# RFM300EVB_V01.net
KiCad netlist of a schematic drawn in Altium Designer
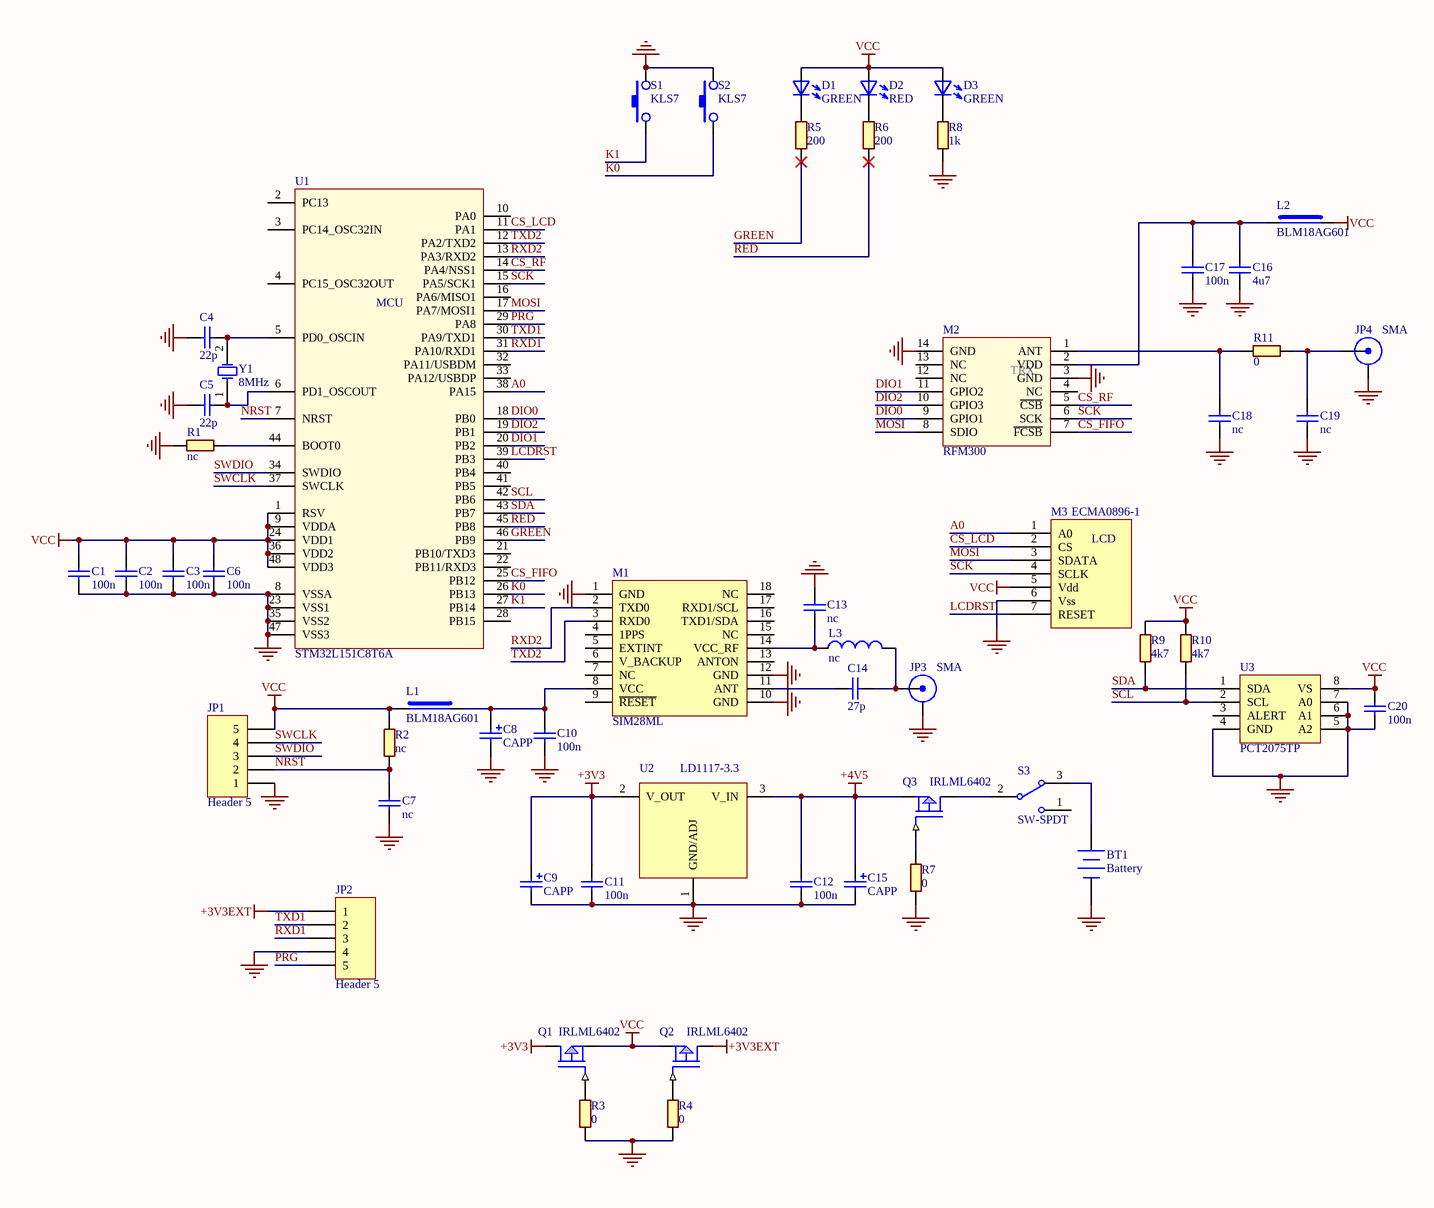
[diagram p0: RFM300EVB_V01.SchDoc]

(export (version "E")
  (design (tool "Eeschema 10.0.6"))
  (components
    (comp (ref "BT1")
      (value "Battery")
      (footprint "3AAAHOLDER")
      (description "Multicell Battery")
      (fields (field (name "PUBLISHER") "Altium Limited"))
      (libsource (lib "Miscellaneous Devices") (part "Battery"))
    )
    (comp (ref "C1") (value "100n") (footprint "C-0603") (libsource (lib "Discrete") (part "CAPN")))
    (comp (ref "C2") (value "100n") (footprint "C-0603") (libsource (lib "Discrete") (part "CAPN")))
    (comp (ref "C3") (value "100n") (footprint "C-0603") (libsource (lib "Discrete") (part "CAPN")))
    (comp (ref "C4") (value "22p") (footprint "C-0603") (libsource (lib "Discrete") (part "CAPN")))
    (comp (ref "C5") (value "22p") (footprint "C-0603") (libsource (lib "Discrete") (part "CAPN")))
    (comp (ref "C6") (value "100n") (footprint "C-0603") (libsource (lib "Discrete") (part "CAPN")))
    (comp (ref "C7") (value "nc") (footprint "C-0603") (libsource (lib "Discrete") (part "CAPN")))
    (comp (ref "C8") (value "CAPP") (footprint "C-TANTAL-B") (libsource (lib "Discrete") (part "CAPP")))
    (comp (ref "C9") (value "CAPP") (footprint "C-TANTAL-B") (libsource (lib "Discrete") (part "CAPP")))
    (comp (ref "C10") (value "100n") (footprint "C-0603") (libsource (lib "Discrete") (part "CAPN")))
    (comp (ref "C11") (value "100n") (footprint "C-0603") (libsource (lib "Discrete") (part "CAPN")))
    (comp (ref "C12") (value "100n") (footprint "C-0603") (libsource (lib "Discrete") (part "CAPN")))
    (comp (ref "C13") (value "nc") (footprint "C-0603") (libsource (lib "Discrete") (part "CAPN")))
    (comp (ref "C14") (value "27p") (footprint "C-0603") (libsource (lib "Discrete") (part "CAPN")))
    (comp (ref "C15") (value "CAPP") (footprint "C-TANTAL-B") (libsource (lib "Discrete") (part "CAPP")))
    (comp (ref "C16") (value "4u7") (footprint "C-0805") (libsource (lib "Discrete") (part "CAPN")))
    (comp (ref "C17") (value "100n") (footprint "C-0603") (libsource (lib "Discrete") (part "CAPN")))
    (comp (ref "C18") (value "nc") (footprint "C-0603") (libsource (lib "Discrete") (part "CAPN")))
    (comp (ref "C19") (value "nc") (footprint "C-0603") (libsource (lib "Discrete") (part "CAPN")))
    (comp (ref "C20") (value "100n") (footprint "C-0603") (libsource (lib "Discrete") (part "CAPN")))
    (comp (ref "D1") (value "GREEN") (footprint "LED_0805") (libsource (lib "Discrete") (part "DLED")))
    (comp (ref "D2") (value "RED") (footprint "LED_0805") (libsource (lib "Discrete") (part "DLED")))
    (comp (ref "D3") (value "GREEN") (footprint "LED_0805") (libsource (lib "Discrete") (part "DLED")))
    (comp (ref "JP1")
      (value "Header 5")
      (footprint "PLS1-5R")
      (description "Header, 5-Pin")
      (fields (field (name "PUBLISHER") "Altium Limited"))
      (libsource (lib "") (part "Header 5_1"))
    )
    (comp (ref "JP2")
      (value "Header 5")
      (footprint "PLS1-5R")
      (description "Header, 5-Pin")
      (fields (field (name "PUBLISHER") "Altium Limited"))
      (libsource (lib "Miscellaneous Connectors") (part "Header 5"))
    )
    (comp (ref "JP3")
      (value "SMA")
      (footprint "AMPHENOL_132357-11")
      (description "RF Connector")
      (libsource (lib "Connectors$switces") (part "X-004"))
    )
    (comp (ref "JP4")
      (value "SMA")
      (footprint "AMPHENOL_132357-11")
      (description "RF Connector")
      (libsource (lib "Connectors$switces") (part "X-004"))
    )
    (comp (ref "L1") (value "BLM18AG601") (footprint "L-0603") (libsource (lib "Discrete") (part "SUPRESOR")))
    (comp (ref "L2") (value "BLM18AG601") (footprint "L-0603") (libsource (lib "Discrete") (part "SUPRESOR")))
    (comp (ref "L3") (value "nc") (footprint "L-0603") (libsource (lib "Discrete") (part "L")))
    (comp (ref "M1")
      (value "SIM28ML")
      (footprint "LGA18_GNSS")
      (libsource (lib "Cellular_GNSS") (part "SIM28ML"))
    )
    (comp (ref "M2")
      (value "RFM300")
      (footprint "LGA14C200P2X7_1600X1600X200")
      (libsource (lib "RFtest") (part "RFM300"))
    )
    (comp (ref "M3") (value "ECMA0896-1") (footprint "PLS1-7") (libsource (lib "RCS-IMS") (part "ECMA0896")))
    (comp (ref "Q1") (value "IRLML6402") (footprint "SOT-23") (libsource (lib "Discrete") (part "IRLML6402")))
    (comp (ref "Q2") (value "IRLML6402") (footprint "SOT-23") (libsource (lib "Discrete") (part "IRLML6402")))
    (comp (ref "Q3") (value "IRLML6402") (footprint "SOT-23") (libsource (lib "Discrete") (part "IRLML6402")))
    (comp (ref "R1") (value "nc") (footprint "R-0603") (libsource (lib "") (part "RES_2")))
    (comp (ref "R2") (value "nc") (footprint "R-0603") (libsource (lib "Discrete") (part "RES")))
    (comp (ref "R3") (value "0") (footprint "R-0603") (libsource (lib "Discrete") (part "RES")))
    (comp (ref "R4") (value "0") (footprint "R-0603") (libsource (lib "Discrete") (part "RES")))
    (comp (ref "R5") (value "200") (footprint "R-0603") (libsource (lib "") (part "RES_1")))
    (comp (ref "R6") (value "200") (footprint "R-0603") (libsource (lib "") (part "RES_1")))
    (comp (ref "R7") (value "0") (footprint "R-0603") (libsource (lib "Discrete") (part "RES")))
    (comp (ref "R8") (value "1k") (footprint "R-0603") (libsource (lib "") (part "RES_1")))
    (comp (ref "R9") (value "4k7") (footprint "R-0603") (libsource (lib "Discrete") (part "RES")))
    (comp (ref "R10") (value "4k7") (footprint "R-0603") (libsource (lib "Discrete") (part "RES")))
    (comp (ref "R11") (value "0") (footprint "R-0603") (libsource (lib "") (part "RES_2")))
    (comp (ref "S1") (value "KLS7") (footprint "KLS7-TS3602") (libsource (lib "CLAP DM-WL-R2") (part "SW-1")))
    (comp (ref "S2") (value "KLS7") (footprint "KLS7-TS3602") (libsource (lib "CLAP DM-WL-R2") (part "SW-1")))
    (comp (ref "S3")
      (value "SW-SPDT")
      (footprint "SPDT_100mil")
      (description "SPDT Subminiature Toggle Switch, Right Angle Mounting, Vertical Actuation")
      (fields (field (name "PUBLISHER") "Altium Limited"))
      (libsource (lib "Miscellaneous Devices") (part "SW-SPDT"))
    )
    (comp (ref "U1")
      (value "STM32L151C8T6A")
      (footprint "LQFP-48")
      (libsource (lib "RFtest") (part "STM32L151C8T6"))
    )
    (comp (ref "U2")
      (value "LD1117-3.3")
      (footprint "SOT230P700X180-4N")
      (libsource (lib "SB") (part "LM1117_3.3"))
    )
    (comp (ref "U3") (value "PCT2075TP") (footprint "SOT1069-2") (libsource (lib "UL2016_v2") (part "TMP75")))
    (comp (ref "Y1")
      (value "8MHz")
      (footprint "HC49_3.5mm")
      (description "Crystal Oscillator")
      (fields (field (name "PUBLISHER") "Altium Limited"))
      (libsource (lib "Miscellaneous Devices") (part "XTAL"))
    )
  )
  (nets
    (net (code "1") (name "+3V3") (class "Default")
      (node (ref "C11") (pin "1") (pinfunction "1_1") (pintype "passive"))
      (node (ref "C9") (pin "2") (pinfunction "2_2") (pintype "passive"))
      (node (ref "Q1") (pin "3") (pinfunction "DRAIN_3") (pintype "passive"))
      (node (ref "U2") (pin "2") (pinfunction "V_OUT_2") (pintype "passive"))
    )
    (net (code "2") (name "+3V3EXT") (class "Default")
      (node (ref "JP2") (pin "1") (pinfunction "1_1") (pintype "passive"))
      (node (ref "Q2") (pin "3") (pinfunction "DRAIN_3") (pintype "passive"))
    )
    (net (code "3") (name "+4V5") (class "Default")
      (node (ref "C12") (pin "1") (pinfunction "1_1") (pintype "passive"))
      (node (ref "C15") (pin "2") (pinfunction "2_2") (pintype "passive"))
      (node (ref "Q3") (pin "2") (pinfunction "SOURCE_2") (pintype "passive"))
      (node (ref "U2") (pin "3") (pinfunction "V_IN_3") (pintype "passive"))
    )
    (net (code "4") (name "/A0") (class "Default")
      (node (ref "M3") (pin "1") (pinfunction "A0_1") (pintype "passive"))
      (node (ref "U1") (pin "38") (pinfunction "PA15_38") (pintype "passive"))
    )
    (net (code "5") (name "/CS_FIFO") (class "Default")
      (node (ref "M2") (pin "7") (pinfunction "~{FCSB}_7") (pintype "passive"))
      (node (ref "U1") (pin "25") (pinfunction "PB12_25") (pintype "passive"))
    )
    (net (code "6") (name "/CS_LCD") (class "Default")
      (node (ref "M3") (pin "2") (pinfunction "CS_2") (pintype "passive"))
      (node (ref "U1") (pin "11") (pinfunction "PA1_11") (pintype "passive"))
    )
    (net (code "7") (name "/CS_RF") (class "Default")
      (node (ref "M2") (pin "5") (pinfunction "~{CSB}_5") (pintype "passive"))
      (node (ref "U1") (pin "14") (pinfunction "PA4/NSS1_14") (pintype "passive"))
    )
    (net (code "8") (name "/DIO0") (class "Default")
      (node (ref "M2") (pin "9") (pinfunction "GPIO1_9") (pintype "passive"))
      (node (ref "U1") (pin "18") (pinfunction "PB0_18") (pintype "passive"))
    )
    (net (code "9") (name "/DIO1") (class "Default")
      (node (ref "M2") (pin "11") (pinfunction "GPIO2_11") (pintype "passive"))
      (node (ref "U1") (pin "20") (pinfunction "PB2_20") (pintype "passive"))
    )
    (net (code "10") (name "/DIO2") (class "Default")
      (node (ref "M2") (pin "10") (pinfunction "GPIO3_10") (pintype "passive"))
      (node (ref "U1") (pin "19") (pinfunction "PB1_19") (pintype "passive"))
    )
    (net (code "11") (name "/GREEN") (class "Default")
      (node (ref "R5") (pin "2") (pinfunction "2_2") (pintype "passive"))
      (node (ref "U1") (pin "46") (pinfunction "PB9_46") (pintype "passive"))
    )
    (net (code "12") (name "/K0") (class "Default")
      (node (ref "S2") (pin "1") (pinfunction "1_1") (pintype "passive"))
      (node (ref "U1") (pin "26") (pinfunction "PB13_26") (pintype "passive"))
    )
    (net (code "13") (name "/K1") (class "Default")
      (node (ref "S1") (pin "1") (pinfunction "1_1") (pintype "passive"))
      (node (ref "U1") (pin "27") (pinfunction "PB14_27") (pintype "passive"))
    )
    (net (code "14") (name "/LCDRST") (class "Default")
      (node (ref "M3") (pin "7") (pinfunction "RESET_7") (pintype "passive"))
      (node (ref "U1") (pin "39") (pinfunction "PB3_39") (pintype "passive"))
    )
    (net (code "15") (name "/MOSI") (class "Default")
      (node (ref "M2") (pin "8") (pinfunction "SDIO_8") (pintype "passive"))
      (node (ref "M3") (pin "3") (pinfunction "SDATA_3") (pintype "passive"))
      (node (ref "U1") (pin "17") (pinfunction "PA7/MOSI1_17") (pintype "passive"))
    )
    (net (code "16") (name "/NRST") (class "Default")
      (node (ref "C7") (pin "1") (pinfunction "1_1") (pintype "passive"))
      (node (ref "JP1") (pin "2") (pinfunction "2_2") (pintype "passive"))
      (node (ref "R2") (pin "1") (pinfunction "1_1") (pintype "passive"))
      (node (ref "U1") (pin "7") (pinfunction "NRST_7") (pintype "passive"))
    )
    (net (code "17") (name "/PRG") (class "Default")
      (node (ref "JP2") (pin "5") (pinfunction "5_5") (pintype "passive"))
      (node (ref "U1") (pin "29") (pinfunction "PA8_29") (pintype "passive"))
    )
    (net (code "18") (name "/RED") (class "Default")
      (node (ref "R6") (pin "2") (pinfunction "2_2") (pintype "passive"))
      (node (ref "U1") (pin "45") (pinfunction "PB8_45") (pintype "passive"))
    )
    (net (code "19") (name "/RXD1") (class "Default")
      (node (ref "JP2") (pin "3") (pinfunction "3_3") (pintype "passive"))
      (node (ref "U1") (pin "31") (pinfunction "PA10/RXD1_31") (pintype "passive"))
    )
    (net (code "20") (name "/RXD2") (class "Default")
      (node (ref "M1") (pin "2") (pinfunction "TXD0_2") (pintype "passive"))
      (node (ref "U1") (pin "13") (pinfunction "PA3/RXD2_13") (pintype "passive"))
    )
    (net (code "21") (name "/SCK") (class "Default")
      (node (ref "M2") (pin "6") (pinfunction "SCK_6") (pintype "passive"))
      (node (ref "M3") (pin "4") (pinfunction "SCLK_4") (pintype "passive"))
      (node (ref "U1") (pin "15") (pinfunction "PA5/SCK1_15") (pintype "passive"))
    )
    (net (code "22") (name "/SCL") (class "Default")
      (node (ref "R10") (pin "1") (pinfunction "1_1") (pintype "passive"))
      (node (ref "U1") (pin "42") (pinfunction "PB6_42") (pintype "passive"))
      (node (ref "U3") (pin "2") (pinfunction "SCL_2") (pintype "passive"))
    )
    (net (code "23") (name "/SDA") (class "Default")
      (node (ref "R9") (pin "1") (pinfunction "1_1") (pintype "passive"))
      (node (ref "U1") (pin "43") (pinfunction "PB7_43") (pintype "passive"))
      (node (ref "U3") (pin "1") (pinfunction "SDA_1") (pintype "passive"))
    )
    (net (code "24") (name "/SWCLK") (class "Default")
      (node (ref "JP1") (pin "4") (pinfunction "4_4") (pintype "passive"))
      (node (ref "U1") (pin "37") (pinfunction "SWCLK_37") (pintype "passive"))
    )
    (net (code "25") (name "/SWDIO") (class "Default")
      (node (ref "JP1") (pin "3") (pinfunction "3_3") (pintype "passive"))
      (node (ref "U1") (pin "34") (pinfunction "SWDIO_34") (pintype "passive"))
    )
    (net (code "26") (name "/TXD1") (class "Default")
      (node (ref "JP2") (pin "2") (pinfunction "2_2") (pintype "passive"))
      (node (ref "U1") (pin "30") (pinfunction "PA9/TXD1_30") (pintype "passive"))
    )
    (net (code "27") (name "/TXD2") (class "Default")
      (node (ref "M1") (pin "3") (pinfunction "RXD0_3") (pintype "passive"))
      (node (ref "U1") (pin "12") (pinfunction "PA2/TXD2_12") (pintype "passive"))
    )
    (net (code "28") (name "GND") (class "Default")
      (node (ref "BT1") (pin "2") (pinfunction "-_2") (pintype "passive"))
      (node (ref "C1") (pin "2") (pinfunction "2_2") (pintype "passive"))
      (node (ref "C10") (pin "2") (pinfunction "2_2") (pintype "passive"))
      (node (ref "C11") (pin "2") (pinfunction "2_2") (pintype "passive"))
      (node (ref "C12") (pin "2") (pinfunction "2_2") (pintype "passive"))
      (node (ref "C13") (pin "1") (pinfunction "1_1") (pintype "passive"))
      (node (ref "C15") (pin "1") (pinfunction "1_1") (pintype "passive"))
      (node (ref "C16") (pin "2") (pinfunction "2_2") (pintype "passive"))
      (node (ref "C17") (pin "2") (pinfunction "2_2") (pintype "passive"))
      (node (ref "C18") (pin "2") (pinfunction "2_2") (pintype "passive"))
      (node (ref "C19") (pin "2") (pinfunction "2_2") (pintype "passive"))
      (node (ref "C2") (pin "2") (pinfunction "2_2") (pintype "passive"))
      (node (ref "C20") (pin "2") (pinfunction "2_2") (pintype "passive"))
      (node (ref "C3") (pin "2") (pinfunction "2_2") (pintype "passive"))
      (node (ref "C4") (pin "1") (pinfunction "1_1") (pintype "passive"))
      (node (ref "C5") (pin "1") (pinfunction "1_1") (pintype "passive"))
      (node (ref "C6") (pin "2") (pinfunction "2_2") (pintype "passive"))
      (node (ref "C7") (pin "2") (pinfunction "2_2") (pintype "passive"))
      (node (ref "C8") (pin "1") (pinfunction "1_1") (pintype "passive"))
      (node (ref "C9") (pin "1") (pinfunction "1_1") (pintype "passive"))
      (node (ref "JP1") (pin "1") (pinfunction "1_1") (pintype "passive"))
      (node (ref "JP2") (pin "4") (pinfunction "4_4") (pintype "passive"))
      (node (ref "JP3") (pin "2") (pinfunction "Y_2") (pintype "passive"))
      (node (ref "JP4") (pin "2") (pinfunction "Y_2") (pintype "passive"))
      (node (ref "M1") (pin "1") (pinfunction "GND_1") (pintype "passive"))
      (node (ref "M1") (pin "10") (pinfunction "GND_10") (pintype "passive"))
      (node (ref "M1") (pin "12") (pinfunction "GND_12") (pintype "passive"))
      (node (ref "M2") (pin "14") (pinfunction "GND_14") (pintype "passive"))
      (node (ref "M2") (pin "3") (pinfunction "GND_3") (pintype "passive"))
      (node (ref "M3") (pin "6") (pinfunction "Vss_6") (pintype "passive"))
      (node (ref "R1") (pin "1") (pinfunction "1_1") (pintype "passive"))
      (node (ref "R3") (pin "1") (pinfunction "1_1") (pintype "passive"))
      (node (ref "R4") (pin "1") (pinfunction "1_1") (pintype "passive"))
      (node (ref "R7") (pin "1") (pinfunction "1_1") (pintype "passive"))
      (node (ref "R8") (pin "2") (pinfunction "2_2") (pintype "passive"))
      (node (ref "S1") (pin "2") (pinfunction "2_2") (pintype "passive"))
      (node (ref "S2") (pin "2") (pinfunction "2_2") (pintype "passive"))
      (node (ref "U1") (pin "23") (pinfunction "VSS1_23") (pintype "passive"))
      (node (ref "U1") (pin "35") (pinfunction "VSS2_35") (pintype "passive"))
      (node (ref "U1") (pin "47") (pinfunction "VSS3_47") (pintype "passive"))
      (node (ref "U1") (pin "8") (pinfunction "VSSA_8") (pintype "passive"))
      (node (ref "U2") (pin "1") (pinfunction "GND/ADJ_1") (pintype "passive"))
      (node (ref "U3") (pin "4") (pinfunction "GND_4") (pintype "passive"))
      (node (ref "U3") (pin "5") (pinfunction "A2_5") (pintype "passive"))
      (node (ref "U3") (pin "6") (pinfunction "A1_6") (pintype "passive"))
      (node (ref "U3") (pin "7") (pinfunction "A0_7") (pintype "passive"))
    )
    (net (code "29") (name "Net-(BT1-+)") (class "Default")
      (node (ref "BT1") (pin "1") (pinfunction "+_1") (pintype "passive"))
      (node (ref "S3") (pin "3") (pinfunction "3_3") (pintype "passive"))
    )
    (net (code "30") (name "Net-(D1-2)") (class "Default")
      (node (ref "D1") (pin "K") (pinfunction "2_K") (pintype "passive"))
      (node (ref "R5") (pin "1") (pinfunction "1_1") (pintype "passive"))
    )
    (net (code "31") (name "Net-(D2-2)") (class "Default")
      (node (ref "D2") (pin "K") (pinfunction "2_K") (pintype "passive"))
      (node (ref "R6") (pin "1") (pinfunction "1_1") (pintype "passive"))
    )
    (net (code "32") (name "Net-(D3-2)") (class "Default")
      (node (ref "D3") (pin "K") (pinfunction "2_K") (pintype "passive"))
      (node (ref "R8") (pin "1") (pinfunction "1_1") (pintype "passive"))
    )
    (net (code "33") (name "Net-(JP3-X)") (class "Default")
      (node (ref "C14") (pin "2") (pinfunction "2_2") (pintype "passive"))
      (node (ref "JP3") (pin "1") (pinfunction "X_1") (pintype "passive"))
      (node (ref "L3") (pin "2") (pinfunction "2_2") (pintype "passive"))
    )
    (net (code "34") (name "Net-(JP4-X)") (class "Default")
      (node (ref "C19") (pin "1") (pinfunction "1_1") (pintype "passive"))
      (node (ref "JP4") (pin "1") (pinfunction "X_1") (pintype "passive"))
      (node (ref "R11") (pin "2") (pinfunction "2_2") (pintype "passive"))
    )
    (net (code "35") (name "Net-(M1-ANT)") (class "Default")
      (node (ref "C14") (pin "1") (pinfunction "1_1") (pintype "passive"))
      (node (ref "M1") (pin "11") (pinfunction "ANT_11") (pintype "passive"))
    )
    (net (code "36") (name "Net-(M1-VCC)") (class "Default")
      (node (ref "C10") (pin "1") (pinfunction "1_1") (pintype "passive"))
      (node (ref "C8") (pin "2") (pinfunction "2_2") (pintype "passive"))
      (node (ref "L1") (pin "2") (pinfunction "2_2") (pintype "passive"))
      (node (ref "M1") (pin "8") (pinfunction "VCC_8") (pintype "passive"))
    )
    (net (code "37") (name "Net-(M1-VCC_RF)") (class "Default")
      (node (ref "C13") (pin "2") (pinfunction "2_2") (pintype "passive"))
      (node (ref "L3") (pin "1") (pinfunction "1_1") (pintype "passive"))
      (node (ref "M1") (pin "14") (pinfunction "VCC_RF_14") (pintype "passive"))
    )
    (net (code "38") (name "Net-(M2-ANT)") (class "Default")
      (node (ref "C18") (pin "1") (pinfunction "1_1") (pintype "passive"))
      (node (ref "M2") (pin "1") (pinfunction "ANT_1") (pintype "passive"))
      (node (ref "R11") (pin "1") (pinfunction "1_1") (pintype "passive"))
    )
    (net (code "39") (name "Net-(M2-VDD)") (class "Default")
      (node (ref "C16") (pin "1") (pinfunction "1_1") (pintype "passive"))
      (node (ref "C17") (pin "1") (pinfunction "1_1") (pintype "passive"))
      (node (ref "L2") (pin "2") (pinfunction "2_2") (pintype "passive"))
      (node (ref "M2") (pin "2") (pinfunction "VDD_2") (pintype "passive"))
    )
    (net (code "40") (name "Net-(Q1-GATE)") (class "Default")
      (node (ref "Q1") (pin "1") (pinfunction "GATE_1") (pintype "input"))
      (node (ref "R3") (pin "2") (pinfunction "2_2") (pintype "passive"))
    )
    (net (code "41") (name "Net-(Q2-GATE)") (class "Default")
      (node (ref "Q2") (pin "1") (pinfunction "GATE_1") (pintype "input"))
      (node (ref "R4") (pin "2") (pinfunction "2_2") (pintype "passive"))
    )
    (net (code "42") (name "Net-(Q3-DRAIN)") (class "Default")
      (node (ref "Q3") (pin "3") (pinfunction "DRAIN_3") (pintype "passive"))
      (node (ref "S3") (pin "2") (pinfunction "2_2") (pintype "passive"))
    )
    (net (code "43") (name "Net-(Q3-GATE)") (class "Default")
      (node (ref "Q3") (pin "1") (pinfunction "GATE_1") (pintype "input"))
      (node (ref "R7") (pin "2") (pinfunction "2_2") (pintype "passive"))
    )
    (net (code "44") (name "Net-(U1-BOOT0)") (class "Default")
      (node (ref "R1") (pin "2") (pinfunction "2_2") (pintype "passive"))
      (node (ref "U1") (pin "44") (pinfunction "BOOT0_44") (pintype "passive"))
    )
    (net (code "45") (name "Net-(U1-PD0_OSCIN)") (class "Default")
      (node (ref "C4") (pin "2") (pinfunction "2_2") (pintype "passive"))
      (node (ref "U1") (pin "5") (pinfunction "PD0_OSCIN_5") (pintype "passive"))
      (node (ref "Y1") (pin "2") (pinfunction "OSC2_2") (pintype "passive"))
    )
    (net (code "46") (name "Net-(U1-PD1_OSCOUT)") (class "Default")
      (node (ref "C5") (pin "2") (pinfunction "2_2") (pintype "passive"))
      (node (ref "U1") (pin "6") (pinfunction "PD1_OSCOUT_6") (pintype "passive"))
      (node (ref "Y1") (pin "1") (pinfunction "OSC1_1") (pintype "passive"))
    )
    (net (code "47") (name "VCC") (class "Default")
      (node (ref "C1") (pin "1") (pinfunction "1_1") (pintype "passive"))
      (node (ref "C2") (pin "1") (pinfunction "1_1") (pintype "passive"))
      (node (ref "C20") (pin "1") (pinfunction "1_1") (pintype "passive"))
      (node (ref "C3") (pin "1") (pinfunction "1_1") (pintype "passive"))
      (node (ref "C6") (pin "1") (pinfunction "1_1") (pintype "passive"))
      (node (ref "D1") (pin "A") (pinfunction "1_A") (pintype "passive"))
      (node (ref "D2") (pin "A") (pinfunction "1_A") (pintype "passive"))
      (node (ref "D3") (pin "A") (pinfunction "1_A") (pintype "passive"))
      (node (ref "JP1") (pin "5") (pinfunction "5_5") (pintype "passive"))
      (node (ref "L1") (pin "1") (pinfunction "1_1") (pintype "passive"))
      (node (ref "L2") (pin "1") (pinfunction "1_1") (pintype "passive"))
      (node (ref "M3") (pin "5") (pinfunction "Vdd_5") (pintype "passive"))
      (node (ref "Q1") (pin "2") (pinfunction "SOURCE_2") (pintype "passive"))
      (node (ref "Q2") (pin "2") (pinfunction "SOURCE_2") (pintype "passive"))
      (node (ref "R10") (pin "2") (pinfunction "2_2") (pintype "passive"))
      (node (ref "R2") (pin "2") (pinfunction "2_2") (pintype "passive"))
      (node (ref "R9") (pin "2") (pinfunction "2_2") (pintype "passive"))
      (node (ref "U1") (pin "1") (pinfunction "RSV_1") (pintype "passive"))
      (node (ref "U1") (pin "24") (pinfunction "VDD1_24") (pintype "passive"))
      (node (ref "U1") (pin "36") (pinfunction "VDD2_36") (pintype "passive"))
      (node (ref "U1") (pin "48") (pinfunction "VDD3_48") (pintype "passive"))
      (node (ref "U1") (pin "9") (pinfunction "VDDA_9") (pintype "passive"))
      (node (ref "U3") (pin "8") (pinfunction "VS_8") (pintype "passive"))
    )
    (net (code "48") (name "unconnected-(M1-1PPS-Pad4)") (class "Default")
      (node (ref "M1") (pin "4") (pinfunction "1PPS_4") (pintype "passive"))
    )
    (net (code "49") (name "unconnected-(M1-ANTON-Pad13)") (class "Default")
      (node (ref "M1") (pin "13") (pinfunction "ANTON_13") (pintype "passive"))
    )
    (net (code "50") (name "unconnected-(M1-EXTINT-Pad5)") (class "Default")
      (node (ref "M1") (pin "5") (pinfunction "EXTINT_5") (pintype "passive"))
    )
    (net (code "51") (name "unconnected-(M1-NC-Pad7)") (class "Default")
      (node (ref "M1") (pin "7") (pinfunction "NC_7") (pintype "passive"))
    )
    (net (code "52") (name "unconnected-(M1-NC-Pad15)") (class "Default")
      (node (ref "M1") (pin "15") (pinfunction "NC_15") (pintype "passive"))
    )
    (net (code "53") (name "unconnected-(M1-NC-Pad18)") (class "Default")
      (node (ref "M1") (pin "18") (pinfunction "NC_18") (pintype "passive"))
    )
    (net (code "54") (name "unconnected-(M1-RXD1{slash}SCL-Pad17)") (class "Default")
      (node (ref "M1") (pin "17") (pinfunction "RXD1/SCL_17") (pintype "passive"))
    )
    (net (code "55") (name "unconnected-(M1-TXD1{slash}SDA-Pad16)") (class "Default")
      (node (ref "M1") (pin "16") (pinfunction "TXD1/SDA_16") (pintype "passive"))
    )
    (net (code "56") (name "unconnected-(M1-V_BACKUP-Pad6)") (class "Default")
      (node (ref "M1") (pin "6") (pinfunction "V_BACKUP_6") (pintype "passive"))
    )
    (net (code "57") (name "unconnected-(M1-~{RESET}-Pad9)") (class "Default")
      (node (ref "M1") (pin "9") (pinfunction "~{RESET}_9") (pintype "passive"))
    )
    (net (code "58") (name "unconnected-(M2-NC-Pad4)") (class "Default")
      (node (ref "M2") (pin "4") (pinfunction "NC_4") (pintype "passive"))
    )
    (net (code "59") (name "unconnected-(M2-NC-Pad12)") (class "Default")
      (node (ref "M2") (pin "12") (pinfunction "NC_12") (pintype "passive"))
    )
    (net (code "60") (name "unconnected-(M2-NC-Pad13)") (class "Default")
      (node (ref "M2") (pin "13") (pinfunction "NC_13") (pintype "passive"))
    )
    (net (code "61") (name "unconnected-(S3-Pad1)") (class "Default")
      (node (ref "S3") (pin "1") (pinfunction "1_1") (pintype "passive"))
    )
    (net (code "62") (name "unconnected-(U1-PA0-Pad10)") (class "Default")
      (node (ref "U1") (pin "10") (pinfunction "PA0_10") (pintype "passive"))
    )
    (net (code "63") (name "unconnected-(U1-PA6{slash}MISO1-Pad16)") (class "Default")
      (node (ref "U1") (pin "16") (pinfunction "PA6/MISO1_16") (pintype "passive"))
    )
    (net (code "64") (name "unconnected-(U1-PA11{slash}USBDM-Pad32)") (class "Default")
      (node (ref "U1") (pin "32") (pinfunction "PA11/USBDM_32") (pintype "passive"))
    )
    (net (code "65") (name "unconnected-(U1-PA12{slash}USBDP-Pad33)") (class "Default")
      (node (ref "U1") (pin "33") (pinfunction "PA12/USBDP_33") (pintype "passive"))
    )
    (net (code "66") (name "unconnected-(U1-PB4-Pad40)") (class "Default")
      (node (ref "U1") (pin "40") (pinfunction "PB4_40") (pintype "passive"))
    )
    (net (code "67") (name "unconnected-(U1-PB5-Pad41)") (class "Default")
      (node (ref "U1") (pin "41") (pinfunction "PB5_41") (pintype "passive"))
    )
    (net (code "68") (name "unconnected-(U1-PB10{slash}TXD3-Pad21)") (class "Default")
      (node (ref "U1") (pin "21") (pinfunction "PB10/TXD3_21") (pintype "passive"))
    )
    (net (code "69") (name "unconnected-(U1-PB11{slash}RXD3-Pad22)") (class "Default")
      (node (ref "U1") (pin "22") (pinfunction "PB11/RXD3_22") (pintype "passive"))
    )
    (net (code "70") (name "unconnected-(U1-PB15-Pad28)") (class "Default")
      (node (ref "U1") (pin "28") (pinfunction "PB15_28") (pintype "passive"))
    )
    (net (code "71") (name "unconnected-(U1-PC13-Pad2)") (class "Default")
      (node (ref "U1") (pin "2") (pinfunction "PC13_2") (pintype "passive"))
    )
    (net (code "72") (name "unconnected-(U1-PC14_OSC32IN-Pad3)") (class "Default")
      (node (ref "U1") (pin "3") (pinfunction "PC14_OSC32IN_3") (pintype "passive"))
    )
    (net (code "73") (name "unconnected-(U1-PC15_OSC32OUT-Pad4)") (class "Default")
      (node (ref "U1") (pin "4") (pinfunction "PC15_OSC32OUT_4") (pintype "passive"))
    )
    (net (code "74") (name "unconnected-(U3-ALERT-Pad3)") (class "Default")
      (node (ref "U3") (pin "3") (pinfunction "ALERT_3") (pintype "passive"))
    )
  )
)
